# Wireless_Power_Transmission_Project.net
KiCad netlist of a schematic drawn in EAGLE
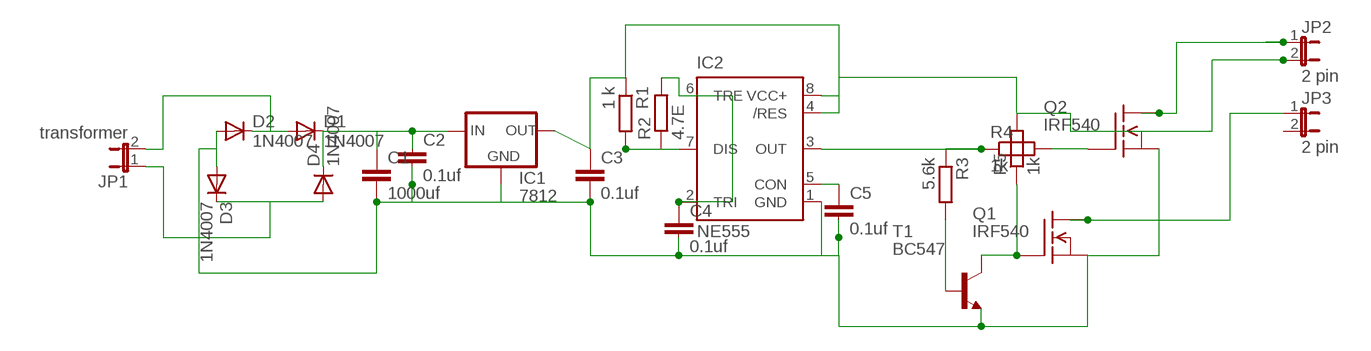
[diagram p0: schematic, sheet 1]

(export (version "E")
  (design (tool "Eeschema 10.0.6"))
  (components
    (comp (ref "C1")
      (value "1000uf")
      (footprint "eagle-import:C2.5-5")
      (libsource (lib "eagle-import") (part "C2.5/5"))
    )
    (comp (ref "C2")
      (value "0.1uf")
      (footprint "eagle-import:C2.5-5")
      (libsource (lib "eagle-import") (part "C2.5/5"))
    )
    (comp (ref "C3")
      (value "0.1uf")
      (footprint "eagle-import:C2.5-5")
      (libsource (lib "eagle-import") (part "C2.5/5"))
    )
    (comp (ref "C4")
      (value "0.1uf")
      (footprint "eagle-import:C2.5-5")
      (libsource (lib "eagle-import") (part "C2.5/5"))
    )
    (comp (ref "C5")
      (value "0.1uf")
      (footprint "eagle-import:C2.5-3")
      (libsource (lib "eagle-import") (part "C2,5-3"))
    )
    (comp (ref "D1")
      (value "1N4007")
      (footprint "eagle-import:DO41-10")
      (libsource (lib "eagle-import") (part "1N4004"))
    )
    (comp (ref "D2")
      (value "1N4007")
      (footprint "eagle-import:DO41-10")
      (libsource (lib "eagle-import") (part "1N4004"))
    )
    (comp (ref "D3")
      (value "1N4007")
      (footprint "eagle-import:DO41-10")
      (libsource (lib "eagle-import") (part "1N4004"))
    )
    (comp (ref "D4")
      (value "1N4007")
      (footprint "eagle-import:DO41-10")
      (libsource (lib "eagle-import") (part "1N4004"))
    )
    (comp (ref "IC1")
      (value "7812")
      (footprint "eagle-import:78XXL")
      (libsource (lib "eagle-import") (part "78XXL"))
    )
    (comp (ref "IC2")
      (value "NE555")
      (footprint "eagle-import:DIL-08")
      (fields (field (name "MF") "Arrow Electronics") (field (name "MPN") "NE555N"))
      (libsource (lib "eagle-import") (part "NE555"))
    )
    (comp (ref "JP1")
      (value "transformer")
      (footprint "eagle-import:JP1")
      (libsource (lib "eagle-import") (part "JP1E"))
    )
    (comp (ref "JP2")
      (value "2 pin")
      (footprint "eagle-import:JP1")
      (libsource (lib "eagle-import") (part "JP1E"))
    )
    (comp (ref "JP3")
      (value "2 pin")
      (footprint "eagle-import:JP1")
      (libsource (lib "eagle-import") (part "JP1E"))
    )
    (comp (ref "Q1")
      (value "IRF540")
      (footprint "eagle-import:TO220")
      (libsource (lib "eagle-import") (part "IRF540"))
    )
    (comp (ref "Q2")
      (value "IRF540")
      (footprint "eagle-import:TO220")
      (libsource (lib "eagle-import") (part "IRF540"))
    )
    (comp (ref "R1")
      (value "1 k")
      (footprint "eagle-import:0204_7")
      (libsource (lib "eagle-import") (part "R-EU_0204/7"))
    )
    (comp (ref "R2")
      (value "4.7E")
      (footprint "eagle-import:0204_7")
      (libsource (lib "eagle-import") (part "R-EU_0204/7"))
    )
    (comp (ref "R3")
      (value "5.6k")
      (footprint "eagle-import:0204_7")
      (libsource (lib "eagle-import") (part "R-EU_0204/7"))
    )
    (comp (ref "R4")
      (value "1k")
      (footprint "eagle-import:0204_7")
      (libsource (lib "eagle-import") (part "R-EU_0204/7"))
    )
    (comp (ref "R5")
      (value "1k")
      (footprint "eagle-import:0204_7")
      (libsource (lib "eagle-import") (part "R-EU_0204/7"))
    )
    (comp (ref "T1")
      (value "BC547")
      (footprint "eagle-import:TO92")
      (libsource (lib "eagle-import") (part "BC547"))
    )
  )
  (nets
    (net (code "1") (name "Net-(C1-Pad1)") (class "Default")
      (node (ref "C1") (pin "1") (pinfunction "1_1") (pintype "passive"))
      (node (ref "C2") (pin "1") (pinfunction "1_1") (pintype "passive"))
      (node (ref "D1") (pin "C") (pinfunction "C_C") (pintype "passive"))
      (node (ref "D4") (pin "C") (pinfunction "C_C") (pintype "passive"))
      (node (ref "IC1") (pin "IN") (pinfunction "IN_IN") (pintype "input"))
    )
    (net (code "2") (name "Net-(D1-PadA)") (class "Default")
      (node (ref "D1") (pin "A") (pinfunction "A_A") (pintype "passive"))
      (node (ref "D2") (pin "C") (pinfunction "C_C") (pintype "passive"))
      (node (ref "JP1") (pin "2") (pinfunction "2_2") (pintype "passive"))
    )
    (net (code "3") (name "Net-(D3-PadC)") (class "Default")
      (node (ref "D3") (pin "C") (pinfunction "C_C") (pintype "passive"))
      (node (ref "D4") (pin "A") (pinfunction "A_A") (pintype "passive"))
      (node (ref "JP1") (pin "1") (pinfunction "1_1") (pintype "passive"))
    )
    (net (code "4") (name "Net-(IC2-CON)") (class "Default")
      (node (ref "C5") (pin "1") (pinfunction "1_1") (pintype "passive"))
      (node (ref "IC2") (pin "5") (pinfunction "CON_5") (pintype "input"))
    )
    (net (code "5") (name "Net-(IC2-DIS)") (class "Default")
      (node (ref "IC2") (pin "7") (pinfunction "DIS_7") (pintype "input"))
      (node (ref "R1") (pin "2") (pinfunction "2_2") (pintype "passive"))
      (node (ref "R2") (pin "1") (pinfunction "1_1") (pintype "passive"))
    )
    (net (code "6") (name "Net-(IC2-GND)") (class "Default")
      (node (ref "C1") (pin "2") (pinfunction "2_2") (pintype "passive"))
      (node (ref "C2") (pin "2") (pinfunction "2_2") (pintype "passive"))
      (node (ref "C3") (pin "2") (pinfunction "2_2") (pintype "passive"))
      (node (ref "C4") (pin "2") (pinfunction "2_2") (pintype "passive"))
      (node (ref "C5") (pin "2") (pinfunction "2_2") (pintype "passive"))
      (node (ref "D2") (pin "A") (pinfunction "A_A") (pintype "passive"))
      (node (ref "D3") (pin "A") (pinfunction "A_A") (pintype "passive"))
      (node (ref "IC1") (pin "GND") (pinfunction "GND_GND") (pintype "input"))
      (node (ref "IC2") (pin "1") (pinfunction "GND_1") (pintype "power_in"))
      (node (ref "Q1") (pin "3") (pinfunction "S_3") (pintype "passive"))
      (node (ref "Q2") (pin "3") (pinfunction "S_3") (pintype "passive"))
      (node (ref "T1") (pin "1") (pinfunction "E_1") (pintype "passive"))
    )
    (net (code "7") (name "Net-(IC2-OUT)") (class "Default")
      (node (ref "IC2") (pin "3") (pinfunction "OUT_3") (pintype "output"))
      (node (ref "R3") (pin "1") (pinfunction "1_1") (pintype "passive"))
      (node (ref "R4") (pin "1") (pinfunction "1_1") (pintype "passive"))
    )
    (net (code "8") (name "Net-(IC2-TRE)") (class "Default")
      (node (ref "C4") (pin "1") (pinfunction "1_1") (pintype "passive"))
      (node (ref "IC2") (pin "2") (pinfunction "TRI_2") (pintype "input"))
      (node (ref "IC2") (pin "6") (pinfunction "TRE_6") (pintype "input"))
      (node (ref "R2") (pin "2") (pinfunction "2_2") (pintype "passive"))
    )
    (net (code "9") (name "Net-(IC2-VCC+)") (class "Default")
      (node (ref "C3") (pin "1") (pinfunction "1_1") (pintype "passive"))
      (node (ref "IC1") (pin "OUT") (pinfunction "OUT_OUT") (pintype "passive"))
      (node (ref "IC2") (pin "4") (pinfunction "/RES_4") (pintype "input"))
      (node (ref "IC2") (pin "8") (pinfunction "VCC+_8") (pintype "power_in"))
      (node (ref "JP2") (pin "2") (pinfunction "2_2") (pintype "passive"))
      (node (ref "R1") (pin "1") (pinfunction "1_1") (pintype "passive"))
      (node (ref "R5") (pin "2") (pinfunction "2_2") (pintype "passive"))
    )
    (net (code "10") (name "Net-(Q1-D)") (class "Default")
      (node (ref "JP3") (pin "1") (pinfunction "1_1") (pintype "passive"))
      (node (ref "Q1") (pin "2") (pinfunction "D_2") (pintype "passive"))
    )
    (net (code "11") (name "Net-(Q1-G)") (class "Default")
      (node (ref "Q1") (pin "1") (pinfunction "G_1") (pintype "passive"))
      (node (ref "R5") (pin "1") (pinfunction "1_1") (pintype "passive"))
      (node (ref "T1") (pin "3") (pinfunction "C_3") (pintype "passive"))
    )
    (net (code "12") (name "Net-(Q2-D)") (class "Default")
      (node (ref "JP2") (pin "1") (pinfunction "1_1") (pintype "passive"))
      (node (ref "Q2") (pin "2") (pinfunction "D_2") (pintype "passive"))
    )
    (net (code "13") (name "Net-(Q2-G)") (class "Default")
      (node (ref "Q2") (pin "1") (pinfunction "G_1") (pintype "passive"))
      (node (ref "R4") (pin "2") (pinfunction "2_2") (pintype "passive"))
    )
    (net (code "14") (name "Net-(T1-B)") (class "Default")
      (node (ref "R3") (pin "2") (pinfunction "2_2") (pintype "passive"))
      (node (ref "T1") (pin "2") (pinfunction "B_2") (pintype "passive"))
    )
    (net (code "15") (name "unconnected-(JP3-Pad2)") (class "Default")
      (node (ref "JP3") (pin "2") (pinfunction "2_2") (pintype "passive"))
    )
  )
)
